# 100_PowerSupply.net
KiCad netlist of a schematic drawn in Altium Designer
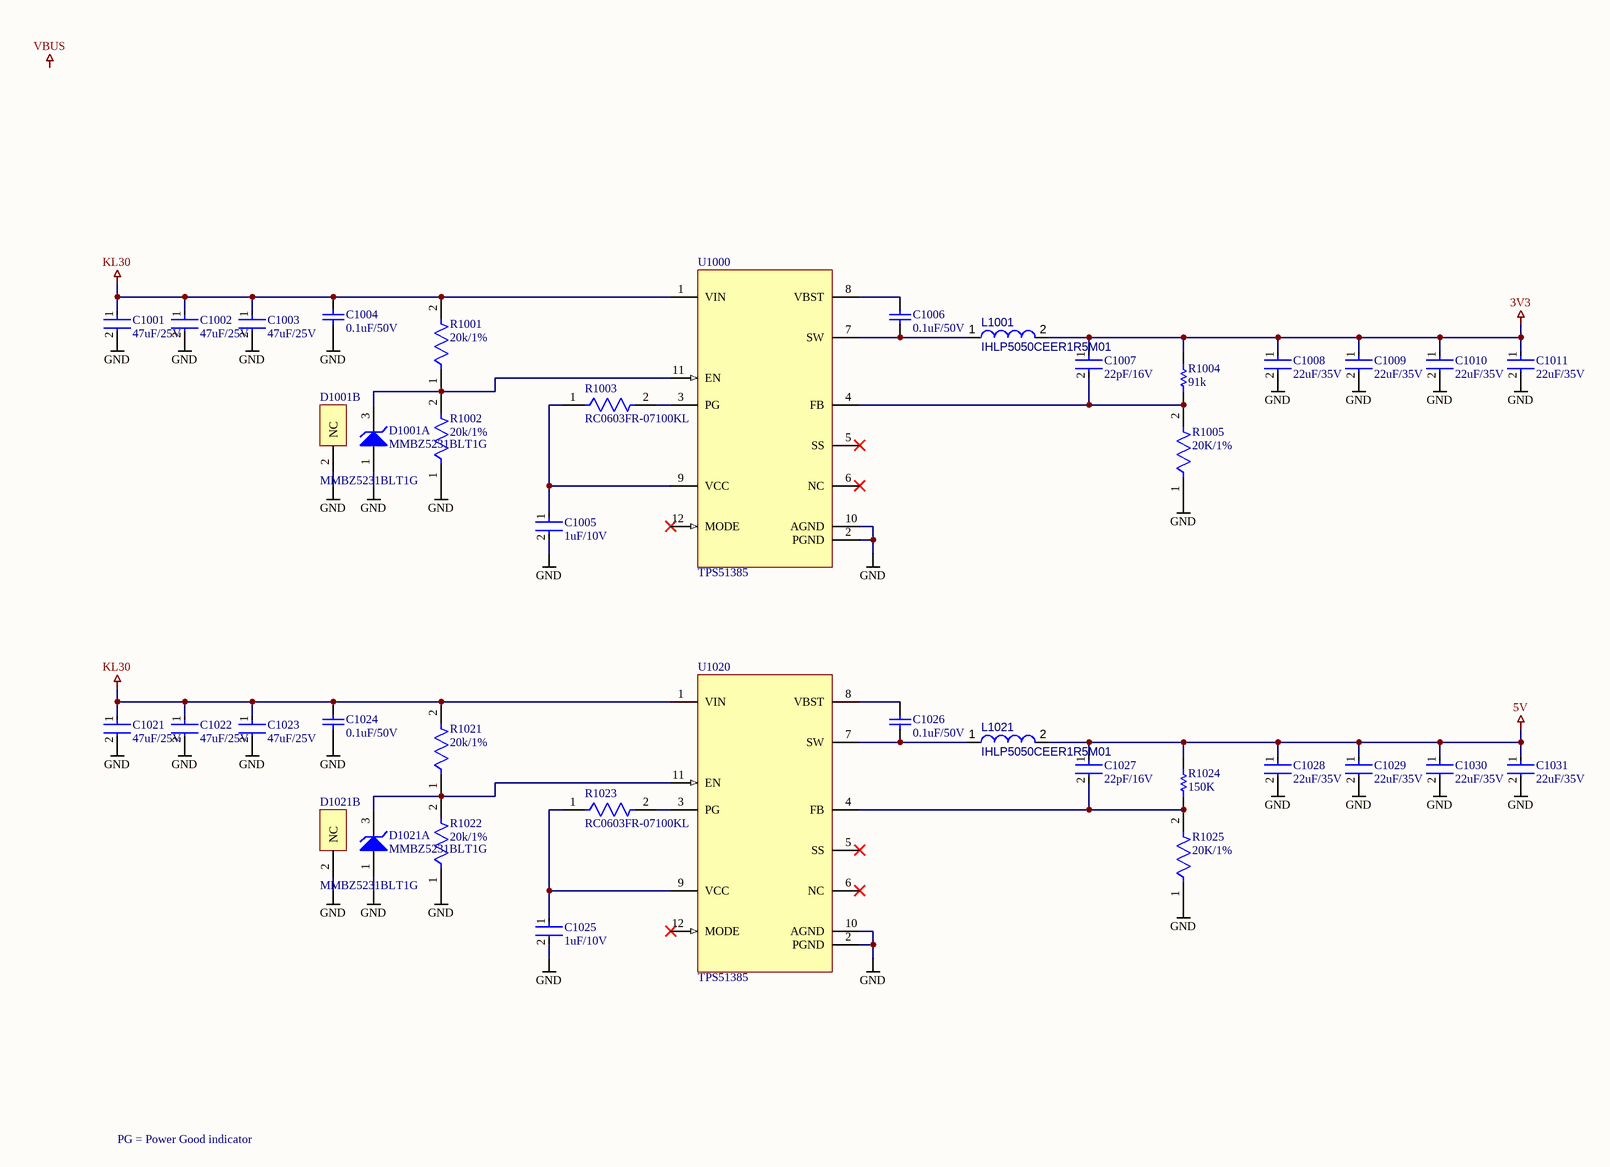
[diagram p0: 100_PowerSupply.SchDoc]

(export (version "E")
  (design (tool "Eeschema 10.0.6"))
  (components
    (comp (ref "C1001")
      (value "47uF/25V")
      (footprint "FP-C3216-160-0_2-MFG")
      (description "Multilayer Ceramic Capacitors 47uF ±20% 25V X5R SMD 1206\r\nC3216X5R1E476M160AC")
      (fields (field (name "VOLTAGE") "25V") (field (name "TOLERANCE") "20%"))
      (libsource (lib "Altium Content Vault") (part "11868f565c42a9108669ba33697ecf6"))
    )
    (comp (ref "C1002")
      (value "47uF/25V")
      (footprint "FP-C3216-160-0_2-MFG")
      (description "Multilayer Ceramic Capacitors 47uF ±20% 25V X5R SMD 1206\r\nC3216X5R1E476M160AC")
      (fields (field (name "VOLTAGE") "25V") (field (name "TOLERANCE") "20%"))
      (libsource (lib "Altium Content Vault") (part "11868f565c42a9108669ba33697ecf6"))
    )
    (comp (ref "C1003")
      (value "47uF/25V")
      (footprint "FP-C3216-160-0_2-MFG")
      (description "Multilayer Ceramic Capacitors 47uF ±20% 25V X5R SMD 1206\r\nC3216X5R1E476M160AC")
      (fields (field (name "VOLTAGE") "25V") (field (name "TOLERANCE") "20%"))
      (libsource (lib "Altium Content Vault") (part "11868f565c42a9108669ba33697ecf6"))
    )
    (comp (ref "C1004")
      (value "0.1uF/50V")
      (footprint "CAPC2013X135X45ML10T25")
      (fields
        (field (name "VOLTAGE") "50V")
        (field (name "TOLERANCE") "10%")
        (field (name "MANUFACTURER") "Murata")
      )
      (libsource (lib "Altium Content Vault") (part "CAP-NP-2"))
    )
    (comp (ref "C1005")
      (value "1uF/10V")
      (footprint "FP-C0603-CG-MFG")
      (description "CAP CER 1UF 10V Y5V 0603\r\nC0603C105Z8VACTU")
      (fields (field (name "TOLERANCE") "80%"))
      (libsource (lib "Altium Content Vault") (part "02cd4be3c70576c341d710602a673aa"))
    )
    (comp (ref "C1006")
      (value "0.1uF/50V")
      (footprint "CAPC2013X135X45ML10T25")
      (fields
        (field (name "VOLTAGE") "50V")
        (field (name "TOLERANCE") "10%")
        (field (name "MANUFACTURER") "Murata")
      )
      (libsource (lib "Altium Content Vault") (part "CAP-NP-2"))
    )
    (comp (ref "C1007")
      (value "22pF/16V")
      (footprint "FP-C0603C-CF-MFG")
      (description "C0603 22 pF C0G 30ppm/°C 10.00% 16 V")
      (fields (field (name "TOLERANCE") "0.1"))
      (libsource (lib "Altium Content Vault") (part "b4654b650e69147ec39a6b967a45e02"))
    )
    (comp (ref "C1008")
      (value "22uF/35V")
      (footprint "FP-C3216-160-0_2-IPC_B")
      (description "Multilayer Ceramic Capacitors 22uF ±20% 35V X5R SMD 1206\r\nC3216X5R1V226M160AC")
      (fields (field (name "TOLERANCE") "20%") (field (name "VOLTAGE") "35V"))
      (libsource (lib "Altium Content Vault") (part "11868f565c42a9108669ba33697ecf6"))
    )
    (comp (ref "C1009")
      (value "22uF/35V")
      (footprint "FP-C3216-160-0_2-IPC_B")
      (description "Multilayer Ceramic Capacitors 22uF ±20% 35V X5R SMD 1206\r\nC3216X5R1V226M160AC")
      (fields (field (name "TOLERANCE") "20%") (field (name "VOLTAGE") "35V"))
      (libsource (lib "Altium Content Vault") (part "11868f565c42a9108669ba33697ecf6"))
    )
    (comp (ref "C1010")
      (value "22uF/35V")
      (footprint "FP-C3216-160-0_2-IPC_B")
      (description "Multilayer Ceramic Capacitors 22uF ±20% 35V X5R SMD 1206\r\nC3216X5R1V226M160AC")
      (fields (field (name "TOLERANCE") "20%") (field (name "VOLTAGE") "35V"))
      (libsource (lib "Altium Content Vault") (part "11868f565c42a9108669ba33697ecf6"))
    )
    (comp (ref "C1011")
      (value "22uF/35V")
      (footprint "FP-C3216-160-0_2-IPC_B")
      (description "Multilayer Ceramic Capacitors 22uF ±20% 35V X5R SMD 1206\r\nC3216X5R1V226M160AC")
      (fields (field (name "TOLERANCE") "20%") (field (name "VOLTAGE") "35V"))
      (libsource (lib "Altium Content Vault") (part "11868f565c42a9108669ba33697ecf6"))
    )
    (comp (ref "C1021")
      (value "47uF/25V")
      (footprint "FP-C3216-160-0_2-MFG")
      (description "Multilayer Ceramic Capacitors 47uF ±20% 25V X5R SMD 1206\r\nC3216X5R1E476M160AC")
      (fields (field (name "VOLTAGE") "25V") (field (name "TOLERANCE") "20%"))
      (libsource (lib "Altium Content Vault") (part "11868f565c42a9108669ba33697ecf6"))
    )
    (comp (ref "C1022")
      (value "47uF/25V")
      (footprint "FP-C3216-160-0_2-MFG")
      (description "Multilayer Ceramic Capacitors 47uF ±20% 25V X5R SMD 1206\r\nC3216X5R1E476M160AC")
      (fields (field (name "VOLTAGE") "25V") (field (name "TOLERANCE") "20%"))
      (libsource (lib "Altium Content Vault") (part "11868f565c42a9108669ba33697ecf6"))
    )
    (comp (ref "C1023")
      (value "47uF/25V")
      (footprint "FP-C3216-160-0_2-MFG")
      (description "Multilayer Ceramic Capacitors 47uF ±20% 25V X5R SMD 1206\r\nC3216X5R1E476M160AC")
      (fields (field (name "VOLTAGE") "25V") (field (name "TOLERANCE") "20%"))
      (libsource (lib "Altium Content Vault") (part "11868f565c42a9108669ba33697ecf6"))
    )
    (comp (ref "C1024")
      (value "0.1uF/50V")
      (footprint "CAPC2013X135X45ML10T25")
      (fields
        (field (name "VOLTAGE") "50V")
        (field (name "TOLERANCE") "10%")
        (field (name "MANUFACTURER") "Murata")
      )
      (libsource (lib "Altium Content Vault") (part "CAP-NP-2"))
    )
    (comp (ref "C1025")
      (value "1uF/10V")
      (footprint "FP-C0603-CG-MFG")
      (description "CAP CER 1UF 10V Y5V 0603\r\nC0603C105Z8VACTU")
      (fields (field (name "TOLERANCE") "80%"))
      (libsource (lib "Altium Content Vault") (part "02cd4be3c70576c341d710602a673aa"))
    )
    (comp (ref "C1026")
      (value "0.1uF/50V")
      (footprint "CAPC2013X135X45ML10T25")
      (fields
        (field (name "VOLTAGE") "50V")
        (field (name "TOLERANCE") "10%")
        (field (name "MANUFACTURER") "Murata")
      )
      (libsource (lib "Altium Content Vault") (part "CAP-NP-2"))
    )
    (comp (ref "C1027")
      (value "22pF/16V")
      (footprint "FP-C0603C-CF-MFG")
      (description "C0603 22 pF C0G 30ppm/°C 10.00% 16 V")
      (fields (field (name "TOLERANCE") "0.1"))
      (libsource (lib "Altium Content Vault") (part "b4654b650e69147ec39a6b967a45e02"))
    )
    (comp (ref "C1028")
      (value "22uF/35V")
      (footprint "FP-C3216-160-0_2-IPC_B")
      (description "Multilayer Ceramic Capacitors 22uF ±20% 35V X5R SMD 1206\r\nC3216X5R1V226M160AC")
      (fields (field (name "TOLERANCE") "20%") (field (name "VOLTAGE") "35V"))
      (libsource (lib "Altium Content Vault") (part "11868f565c42a9108669ba33697ecf6"))
    )
    (comp (ref "C1029")
      (value "22uF/35V")
      (footprint "FP-C3216-160-0_2-IPC_B")
      (description "Multilayer Ceramic Capacitors 22uF ±20% 35V X5R SMD 1206\r\nC3216X5R1V226M160AC")
      (fields (field (name "TOLERANCE") "20%") (field (name "VOLTAGE") "35V"))
      (libsource (lib "Altium Content Vault") (part "11868f565c42a9108669ba33697ecf6"))
    )
    (comp (ref "C1030")
      (value "22uF/35V")
      (footprint "FP-C3216-160-0_2-IPC_B")
      (description "Multilayer Ceramic Capacitors 22uF ±20% 35V X5R SMD 1206\r\nC3216X5R1V226M160AC")
      (fields (field (name "TOLERANCE") "20%") (field (name "VOLTAGE") "35V"))
      (libsource (lib "Altium Content Vault") (part "11868f565c42a9108669ba33697ecf6"))
    )
    (comp (ref "C1031")
      (value "22uF/35V")
      (footprint "FP-C3216-160-0_2-IPC_B")
      (description "Multilayer Ceramic Capacitors 22uF ±20% 35V X5R SMD 1206\r\nC3216X5R1V226M160AC")
      (fields (field (name "TOLERANCE") "20%") (field (name "VOLTAGE") "35V"))
      (libsource (lib "Altium Content Vault") (part "11868f565c42a9108669ba33697ecf6"))
    )
    (comp (ref "D1001")
      (value "MMBZ5231BLT1G")
      (footprint "ONSC-SOT-23-3-318-08_V")
      (description "Zener Voltage Regulator, 225 mW, 3-Pin SOT-23, Pb-Free, Tape and Reel")
      (fields (field (name "MANUFACTURER") "On Semiconductor"))
      (libsource (lib "Altium Content Vault") (part "ONSC-A1K3-3"))
    )
    (comp (ref "D1021")
      (value "MMBZ5231BLT1G")
      (footprint "ONSC-SOT-23-3-318-08_V")
      (description "Zener Voltage Regulator, 225 mW, 3-Pin SOT-23, Pb-Free, Tape and Reel")
      (fields (field (name "MANUFACTURER") "On Semiconductor"))
      (libsource (lib "Altium Content Vault") (part "ONSC-A1K3-3"))
    )
    (comp (ref "L1001")
      (value "IHLP5050CEER1R5M01")
      (footprint "IHLP5050CEER1R5M01")
      (description "Chip Inductor, 1.5 uH, +/- 20%\r\nIHLP5050CEER1R5M01")
      (libsource (lib "AltiumLib_MILUTIN") (part "IHLP5050CEER1R5M01"))
    )
    (comp (ref "L1021")
      (value "IHLP5050CEER1R5M01")
      (footprint "IHLP5050CEER1R5M01")
      (description "Chip Inductor, 1.5 uH, +/- 20%\r\nIHLP5050CEER1R5M01")
      (libsource (lib "AltiumLib_MILUTIN") (part "IHLP5050CEER1R5M01"))
    )
    (comp (ref "R1001")
      (value "20k/1%")
      (footprint "FP-RC0603-0_55-IPC_C")
      (description "RES 20K OHM 1% 1/10W 0603\r\nRC0603FR-0720KL")
      (fields (field (name "TOLERANCE") "1%"))
      (libsource (lib "Altium Content Vault") (part "1029c3af85768c4190bb7ad29bc67b5"))
    )
    (comp (ref "R1002")
      (value "20k/1%")
      (footprint "FP-RC0603-0_55-IPC_C")
      (description "RES 20K OHM 1% 1/10W 0603\r\nRC0603FR-0720KL")
      (fields (field (name "TOLERANCE") "1%"))
      (libsource (lib "Altium Content Vault") (part "1029c3af85768c4190bb7ad29bc67b5"))
    )
    (comp (ref "R1003")
      (value "RC0603FR-07100KL")
      (footprint "FP-RC0603-0_55-MFG")
      (description "RES SMD 100K OHM 1% 1/10W 0603")
      (fields (field (name "TOLERANCE") "1%"))
      (libsource (lib "Altium Content Vault") (part "1029c3af85768c4190bb7ad29bc67b5"))
    )
    (comp (ref "R1004")
      (value "91k")
      (footprint "RESC1609X50X30NL10T20")
      (description "CRCW060391K0FKEA")
      (fields (field (name "MANUFACTURER") "Vishay Dale"))
      (libsource (lib "Altium Content Vault") (part "RES"))
    )
    (comp (ref "R1005")
      (value "20K/1%")
      (footprint "FP-RC0603-0_55-IPC_C")
      (description "RES 20K OHM 1% 1/10W 0603\r\nRC0603FR-0720KL")
      (fields (field (name "TOLERANCE") "1%"))
      (libsource (lib "Altium Content Vault") (part "1029c3af85768c4190bb7ad29bc67b5"))
    )
    (comp (ref "R1021")
      (value "20k/1%")
      (footprint "FP-RC0603-0_55-IPC_C")
      (description "RES 20K OHM 1% 1/10W 0603\r\nRC0603FR-0720KL")
      (fields (field (name "TOLERANCE") "1%"))
      (libsource (lib "Altium Content Vault") (part "1029c3af85768c4190bb7ad29bc67b5"))
    )
    (comp (ref "R1022")
      (value "20k/1%")
      (footprint "FP-RC0603-0_55-IPC_C")
      (description "RES 20K OHM 1% 1/10W 0603\r\nRC0603FR-0720KL")
      (fields (field (name "TOLERANCE") "1%"))
      (libsource (lib "Altium Content Vault") (part "1029c3af85768c4190bb7ad29bc67b5"))
    )
    (comp (ref "R1023")
      (value "RC0603FR-07100KL")
      (footprint "FP-RC0603-0_55-MFG")
      (description "RES SMD 100K OHM 1% 1/10W 0603")
      (fields (field (name "TOLERANCE") "1%"))
      (libsource (lib "Altium Content Vault") (part "1029c3af85768c4190bb7ad29bc67b5"))
    )
    (comp (ref "R1024")
      (value "150K")
      (footprint "RESC1608X55X30NL15T15")
      (description "ERJ-3EKF1503V")
      (fields (field (name "MANUFACTURER") "Panasonic"))
      (libsource (lib "Altium Content Vault") (part "RES"))
    )
    (comp (ref "R1025")
      (value "20K/1%")
      (footprint "FP-RC0603-0_55-IPC_C")
      (description "RES 20K OHM 1% 1/10W 0603\r\nRC0603FR-0720KL")
      (fields (field (name "TOLERANCE") "1%"))
      (libsource (lib "Altium Content Vault") (part "1029c3af85768c4190bb7ad29bc67b5"))
    )
    (comp (ref "U1000")
      (value "TPS51385")
      (footprint "TPS51386")
      (description "8A Synchronous Buck Converter - TPS51386")
      (libsource (lib "AltiumLib_MILUTIN") (part "TPS51386"))
    )
    (comp (ref "U1020")
      (value "TPS51385")
      (footprint "TPS51386")
      (description "8A Synchronous Buck Converter - TPS51386")
      (libsource (lib "AltiumLib_MILUTIN") (part "TPS51386"))
    )
  )
  (nets
    (net (code "1") (name "3V3") (class "Default")
      (node (ref "C1007") (pin "1") (pinfunction "1_1") (pintype "passive"))
      (node (ref "C1008") (pin "1") (pinfunction "1_1") (pintype "passive"))
      (node (ref "C1009") (pin "1") (pinfunction "1_1") (pintype "passive"))
      (node (ref "C1010") (pin "1") (pinfunction "1_1") (pintype "passive"))
      (node (ref "C1011") (pin "1") (pinfunction "1_1") (pintype "passive"))
      (node (ref "L1001") (pin "2") (pinfunction "2_2") (pintype "passive"))
      (node (ref "R1004") (pin "2") (pinfunction "2_2") (pintype "passive"))
    )
    (net (code "2") (name "5V") (class "Default")
      (node (ref "C1027") (pin "1") (pinfunction "1_1") (pintype "passive"))
      (node (ref "C1028") (pin "1") (pinfunction "1_1") (pintype "passive"))
      (node (ref "C1029") (pin "1") (pinfunction "1_1") (pintype "passive"))
      (node (ref "C1030") (pin "1") (pinfunction "1_1") (pintype "passive"))
      (node (ref "C1031") (pin "1") (pinfunction "1_1") (pintype "passive"))
      (node (ref "L1021") (pin "2") (pinfunction "2_2") (pintype "passive"))
      (node (ref "R1024") (pin "2") (pinfunction "2_2") (pintype "passive"))
    )
    (net (code "3") (name "GND") (class "Default")
      (node (ref "C1001") (pin "2") (pinfunction "2_2") (pintype "passive"))
      (node (ref "C1002") (pin "2") (pinfunction "2_2") (pintype "passive"))
      (node (ref "C1003") (pin "2") (pinfunction "2_2") (pintype "passive"))
      (node (ref "C1004") (pin "1") (pinfunction "1_1") (pintype "passive"))
      (node (ref "C1005") (pin "2") (pinfunction "2_2") (pintype "passive"))
      (node (ref "C1008") (pin "2") (pinfunction "2_2") (pintype "passive"))
      (node (ref "C1009") (pin "2") (pinfunction "2_2") (pintype "passive"))
      (node (ref "C1010") (pin "2") (pinfunction "2_2") (pintype "passive"))
      (node (ref "C1011") (pin "2") (pinfunction "2_2") (pintype "passive"))
      (node (ref "C1021") (pin "2") (pinfunction "2_2") (pintype "passive"))
      (node (ref "C1022") (pin "2") (pinfunction "2_2") (pintype "passive"))
      (node (ref "C1023") (pin "2") (pinfunction "2_2") (pintype "passive"))
      (node (ref "C1024") (pin "1") (pinfunction "1_1") (pintype "passive"))
      (node (ref "C1025") (pin "2") (pinfunction "2_2") (pintype "passive"))
      (node (ref "C1028") (pin "2") (pinfunction "2_2") (pintype "passive"))
      (node (ref "C1029") (pin "2") (pinfunction "2_2") (pintype "passive"))
      (node (ref "C1030") (pin "2") (pinfunction "2_2") (pintype "passive"))
      (node (ref "C1031") (pin "2") (pinfunction "2_2") (pintype "passive"))
      (node (ref "D1001") (pin "1") (pinfunction "A_1") (pintype "passive"))
      (node (ref "D1001") (pin "2") (pinfunction "NC_2") (pintype "passive"))
      (node (ref "D1021") (pin "1") (pinfunction "A_1") (pintype "passive"))
      (node (ref "D1021") (pin "2") (pinfunction "NC_2") (pintype "passive"))
      (node (ref "R1002") (pin "1") (pinfunction "1_1") (pintype "passive"))
      (node (ref "R1005") (pin "1") (pinfunction "1_1") (pintype "passive"))
      (node (ref "R1022") (pin "1") (pinfunction "1_1") (pintype "passive"))
      (node (ref "R1025") (pin "1") (pinfunction "1_1") (pintype "passive"))
      (node (ref "U1000") (pin "10") (pinfunction "AGND_10") (pintype "passive"))
      (node (ref "U1000") (pin "2") (pinfunction "PGND_2") (pintype "passive"))
      (node (ref "U1020") (pin "10") (pinfunction "AGND_10") (pintype "passive"))
      (node (ref "U1020") (pin "2") (pinfunction "PGND_2") (pintype "passive"))
    )
    (net (code "4") (name "KL30") (class "Default")
      (node (ref "C1001") (pin "1") (pinfunction "1_1") (pintype "passive"))
      (node (ref "C1002") (pin "1") (pinfunction "1_1") (pintype "passive"))
      (node (ref "C1003") (pin "1") (pinfunction "1_1") (pintype "passive"))
      (node (ref "C1004") (pin "2") (pinfunction "2_2") (pintype "passive"))
      (node (ref "C1021") (pin "1") (pinfunction "1_1") (pintype "passive"))
      (node (ref "C1022") (pin "1") (pinfunction "1_1") (pintype "passive"))
      (node (ref "C1023") (pin "1") (pinfunction "1_1") (pintype "passive"))
      (node (ref "C1024") (pin "2") (pinfunction "2_2") (pintype "passive"))
      (node (ref "R1001") (pin "2") (pinfunction "2_2") (pintype "passive"))
      (node (ref "R1021") (pin "2") (pinfunction "2_2") (pintype "passive"))
      (node (ref "U1000") (pin "1") (pinfunction "VIN_1") (pintype "passive"))
      (node (ref "U1020") (pin "1") (pinfunction "VIN_1") (pintype "passive"))
    )
    (net (code "5") (name "Net-(D1001A-K)") (class "Default")
      (node (ref "D1001") (pin "3") (pinfunction "K_3") (pintype "passive"))
      (node (ref "R1001") (pin "1") (pinfunction "1_1") (pintype "passive"))
      (node (ref "R1002") (pin "2") (pinfunction "2_2") (pintype "passive"))
      (node (ref "U1000") (pin "11") (pinfunction "EN_11") (pintype "input"))
    )
    (net (code "6") (name "Net-(D1021A-K)") (class "Default")
      (node (ref "D1021") (pin "3") (pinfunction "K_3") (pintype "passive"))
      (node (ref "R1021") (pin "1") (pinfunction "1_1") (pintype "passive"))
      (node (ref "R1022") (pin "2") (pinfunction "2_2") (pintype "passive"))
      (node (ref "U1020") (pin "11") (pinfunction "EN_11") (pintype "input"))
    )
    (net (code "7") (name "Net-(U1000-FB)") (class "Default")
      (node (ref "C1007") (pin "2") (pinfunction "2_2") (pintype "passive"))
      (node (ref "R1004") (pin "1") (pinfunction "1_1") (pintype "passive"))
      (node (ref "R1005") (pin "2") (pinfunction "2_2") (pintype "passive"))
      (node (ref "U1000") (pin "4") (pinfunction "FB_4") (pintype "passive"))
    )
    (net (code "8") (name "Net-(U1000-PG)") (class "Default")
      (node (ref "R1003") (pin "2") (pinfunction "2_2") (pintype "passive"))
      (node (ref "U1000") (pin "3") (pinfunction "PG_3") (pintype "passive"))
    )
    (net (code "9") (name "Net-(U1000-SW)") (class "Default")
      (node (ref "C1006") (pin "1") (pinfunction "1_1") (pintype "passive"))
      (node (ref "L1001") (pin "1") (pinfunction "1_1") (pintype "passive"))
      (node (ref "U1000") (pin "7") (pinfunction "SW_7") (pintype "passive"))
    )
    (net (code "10") (name "Net-(U1000-VBST)") (class "Default")
      (node (ref "C1006") (pin "2") (pinfunction "2_2") (pintype "passive"))
      (node (ref "U1000") (pin "8") (pinfunction "VBST_8") (pintype "passive"))
    )
    (net (code "11") (name "Net-(U1000-VCC)") (class "Default")
      (node (ref "C1005") (pin "1") (pinfunction "1_1") (pintype "passive"))
      (node (ref "R1003") (pin "1") (pinfunction "1_1") (pintype "passive"))
      (node (ref "U1000") (pin "9") (pinfunction "VCC_9") (pintype "passive"))
    )
    (net (code "12") (name "Net-(U1020-FB)") (class "Default")
      (node (ref "C1027") (pin "2") (pinfunction "2_2") (pintype "passive"))
      (node (ref "R1024") (pin "1") (pinfunction "1_1") (pintype "passive"))
      (node (ref "R1025") (pin "2") (pinfunction "2_2") (pintype "passive"))
      (node (ref "U1020") (pin "4") (pinfunction "FB_4") (pintype "passive"))
    )
    (net (code "13") (name "Net-(U1020-PG)") (class "Default")
      (node (ref "R1023") (pin "2") (pinfunction "2_2") (pintype "passive"))
      (node (ref "U1020") (pin "3") (pinfunction "PG_3") (pintype "passive"))
    )
    (net (code "14") (name "Net-(U1020-SW)") (class "Default")
      (node (ref "C1026") (pin "1") (pinfunction "1_1") (pintype "passive"))
      (node (ref "L1021") (pin "1") (pinfunction "1_1") (pintype "passive"))
      (node (ref "U1020") (pin "7") (pinfunction "SW_7") (pintype "passive"))
    )
    (net (code "15") (name "Net-(U1020-VBST)") (class "Default")
      (node (ref "C1026") (pin "2") (pinfunction "2_2") (pintype "passive"))
      (node (ref "U1020") (pin "8") (pinfunction "VBST_8") (pintype "passive"))
    )
    (net (code "16") (name "Net-(U1020-VCC)") (class "Default")
      (node (ref "C1025") (pin "1") (pinfunction "1_1") (pintype "passive"))
      (node (ref "R1023") (pin "1") (pinfunction "1_1") (pintype "passive"))
      (node (ref "U1020") (pin "9") (pinfunction "VCC_9") (pintype "passive"))
    )
    (net (code "18") (name "unconnected-(U1000-MODE-Pad12)") (class "Default")
      (node (ref "U1000") (pin "12") (pinfunction "MODE_12") (pintype "input+no_connect"))
    )
    (net (code "19") (name "unconnected-(U1000-NC-Pad6)") (class "Default")
      (node (ref "U1000") (pin "6") (pinfunction "NC_6") (pintype "passive+no_connect"))
    )
    (net (code "20") (name "unconnected-(U1000-SS-Pad5)") (class "Default")
      (node (ref "U1000") (pin "5") (pinfunction "SS_5") (pintype "passive+no_connect"))
    )
    (net (code "21") (name "unconnected-(U1020-MODE-Pad12)") (class "Default")
      (node (ref "U1020") (pin "12") (pinfunction "MODE_12") (pintype "input+no_connect"))
    )
    (net (code "22") (name "unconnected-(U1020-NC-Pad6)") (class "Default")
      (node (ref "U1020") (pin "6") (pinfunction "NC_6") (pintype "passive+no_connect"))
    )
    (net (code "23") (name "unconnected-(U1020-SS-Pad5)") (class "Default")
      (node (ref "U1020") (pin "5") (pinfunction "SS_5") (pintype "passive+no_connect"))
    )
  )
)
